# MCU.net
KiCad netlist of a schematic drawn in Altium Designer
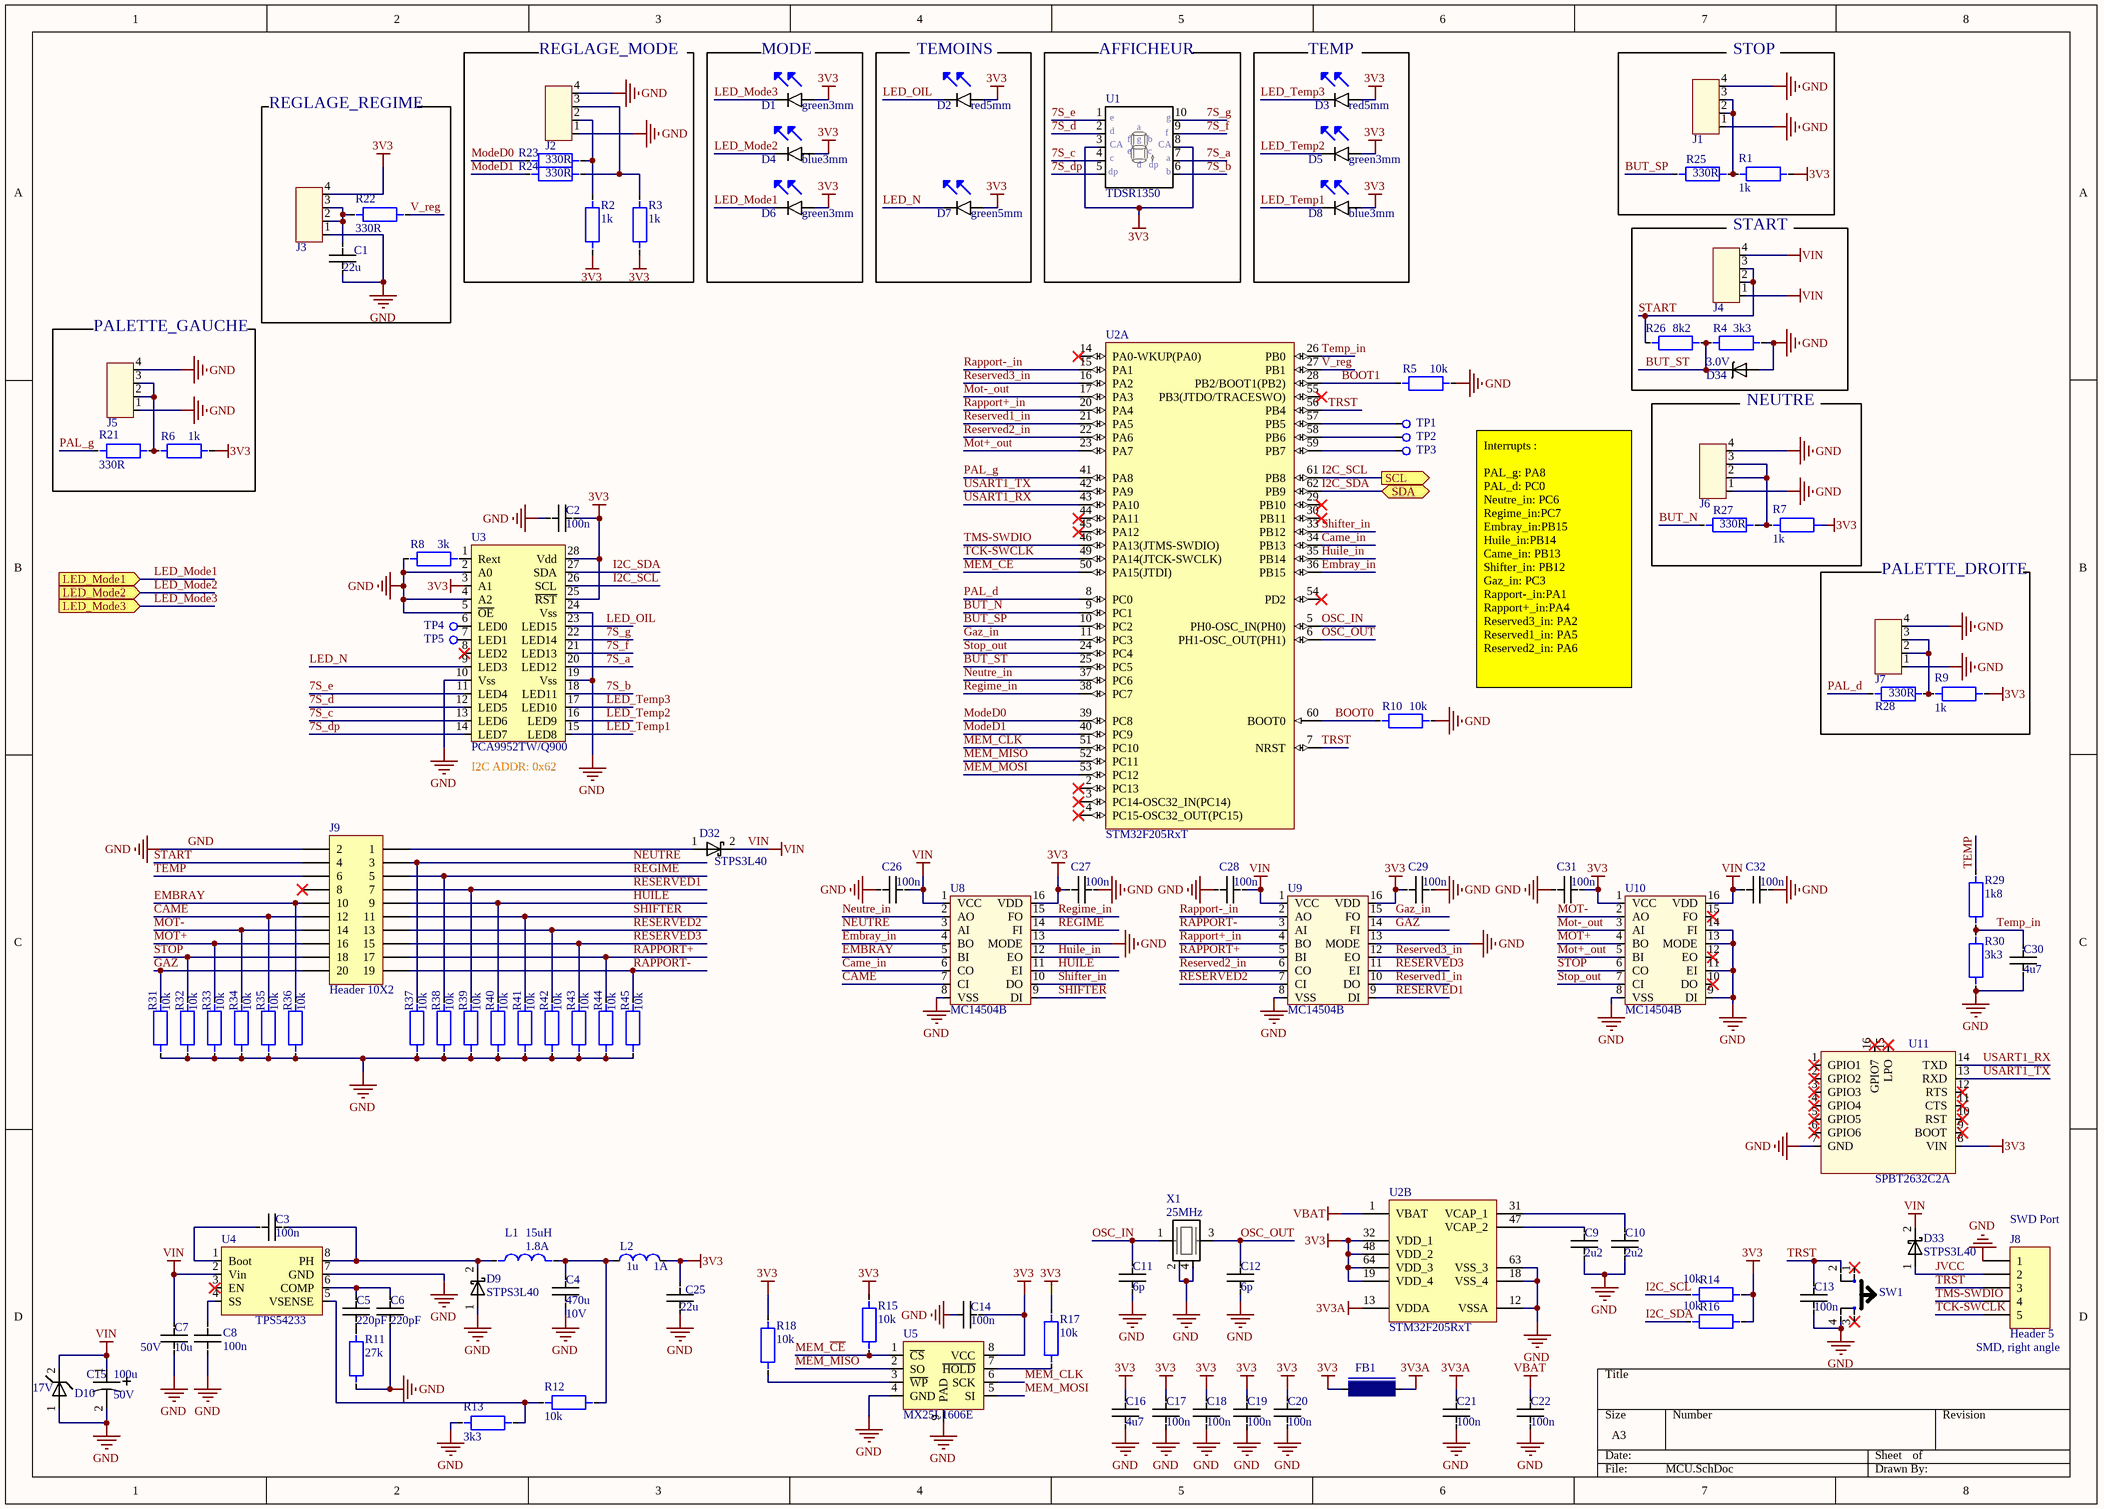
[diagram p0: MCU.SchDoc]

(export (version "E")
  (design (tool "Eeschema 10.0.6"))
  (components
    (comp (ref "C1")
      (value "22u")
      (footprint "0805_")
      (fields
        (field (name "MANUFACTURER PARTNUM") "GRM21BR61A226ME51L")
        (field (name "MANUFACTURER") "Murata")
      )
      (libsource (lib "*") (part "C"))
    )
    (comp (ref "C2")
      (value "100n")
      (footprint "0402_")
      (fields
        (field (name "MANUFACTURER PARTNUM") "C1005X5R1E104K050BC")
        (field (name "MANUFACTURER") "TDK Corp")
      )
      (libsource (lib "*") (part "C"))
    )
    (comp (ref "C3")
      (value "100n")
      (footprint "0402_")
      (fields
        (field (name "MANUFACTURER PARTNUM") "C1005X5R1E104K050BC")
        (field (name "MANUFACTURER") "TDK Corp")
      )
      (libsource (lib "*") (part "C"))
    )
    (comp (ref "C4")
      (value "470u")
      (footprint "2917")
      (fields
        (field (name "VOLTAGE") "10V")
        (field (name "MANUFACTURER PARTNUM") "T495X477K010ATE100")
        (field (name "MANUFACTURER") "Kemet")
        (field (name "Comment") "C")
      )
      (libsource (lib "*") (part "C"))
    )
    (comp (ref "C5")
      (value "220pF")
      (footprint "0402_")
      (fields
        (field (name "MANUFACTURER PARTNUM") "CL05B221KB5NNNC")
        (field (name "MANUFACTURER") "Samsung")
        (field (name "Comment") "C")
      )
      (libsource (lib "*") (part "C"))
    )
    (comp (ref "C6")
      (value "220pF")
      (footprint "0402_")
      (fields
        (field (name "MANUFACTURER PARTNUM") "CL05B221KB5NNNC")
        (field (name "MANUFACTURER") "Samsung")
        (field (name "Comment") "C")
      )
      (libsource (lib "*") (part "C"))
    )
    (comp (ref "C7")
      (value "10u")
      (footprint "1206_")
      (fields
        (field (name "RATED VOLTAGE") "50V")
        (field (name "MANUFACTURER PARTNUM") "CL31A106KBHNNNE")
        (field (name "MANUFACTURER") "Samsung")
      )
      (libsource (lib "*") (part "C"))
    )
    (comp (ref "C8")
      (value "100n")
      (footprint "0402_")
      (fields
        (field (name "MANUFACTURER PARTNUM") "C1005X5R1E104K050BC")
        (field (name "MANUFACTURER") "TDK Corp")
      )
      (libsource (lib "*") (part "C"))
    )
    (comp (ref "C9")
      (value "2u2")
      (footprint "0402_")
      (fields
        (field (name "MANUFACTURER PARTNUM") "GRM155R61A225KE95D")
        (field (name "MANUFACTURER") "Murata")
        (field (name "VOLTAGE") "10V")
      )
      (libsource (lib "*") (part "C"))
    )
    (comp (ref "C10")
      (value "2u2")
      (footprint "0402_")
      (fields
        (field (name "MANUFACTURER PARTNUM") "GRM155R61A225KE95D")
        (field (name "MANUFACTURER") "Murata")
        (field (name "VOLTAGE") "10V")
      )
      (libsource (lib "*") (part "C"))
    )
    (comp (ref "C11")
      (value "6p")
      (footprint "0402_")
      (fields (field (name "MANUFACTURER") "Samsung") (field (name "MANUFACTURER PARTNUM") "CL05C060DB5NCNC"))
      (libsource (lib "*") (part "C"))
    )
    (comp (ref "C12")
      (value "6p")
      (footprint "0402_")
      (fields (field (name "MANUFACTURER") "Samsung") (field (name "MANUFACTURER PARTNUM") "CL05C060DB5NCNC"))
      (libsource (lib "*") (part "C"))
    )
    (comp (ref "C13")
      (value "100n")
      (footprint "0402_")
      (fields
        (field (name "MANUFACTURER PARTNUM") "C1005X5R1E104K050BC")
        (field (name "MANUFACTURER") "TDK Corp")
      )
      (libsource (lib "*") (part "C"))
    )
    (comp (ref "C14")
      (value "100n")
      (footprint "0402_")
      (fields
        (field (name "MANUFACTURER PARTNUM") "C1005X5R1E104K050BC")
        (field (name "MANUFACTURER") "TDK Corp")
      )
      (libsource (lib "*") (part "C"))
    )
    (comp (ref "C15")
      (value "100u")
      (footprint "C_pol8x12mm")
      (fields
        (field (name "RATED VOLTAGE") "50V")
        (field (name "MANUFACTURER") "Nichicon")
        (field (name "MANUFACTURER PARTNUM") "UVR1H101MPD1TD")
        (field (name "Comment") "C_pol")
      )
      (libsource (lib "Sch_GB_lib") (part "C_pol"))
    )
    (comp (ref "C16")
      (value "4u7")
      (footprint "0402_")
      (fields
        (field (name "MANUFACTURER") "Murata")
        (field (name "MANUFACTURER PARTNUM") "GRM155R60J475ME47D")
      )
      (libsource (lib "*") (part "C"))
    )
    (comp (ref "C17")
      (value "100n")
      (footprint "0402_")
      (fields
        (field (name "MANUFACTURER PARTNUM") "C1005X5R1E104K050BC")
        (field (name "MANUFACTURER") "TDK Corp")
      )
      (libsource (lib "*") (part "C"))
    )
    (comp (ref "C18")
      (value "100n")
      (footprint "0402_")
      (fields
        (field (name "MANUFACTURER PARTNUM") "C1005X5R1E104K050BC")
        (field (name "MANUFACTURER") "TDK Corp")
      )
      (libsource (lib "*") (part "C"))
    )
    (comp (ref "C19")
      (value "100n")
      (footprint "0402_")
      (fields
        (field (name "MANUFACTURER PARTNUM") "C1005X5R1E104K050BC")
        (field (name "MANUFACTURER") "TDK Corp")
      )
      (libsource (lib "*") (part "C"))
    )
    (comp (ref "C20")
      (value "100n")
      (footprint "0402_")
      (fields
        (field (name "MANUFACTURER PARTNUM") "C1005X5R1E104K050BC")
        (field (name "MANUFACTURER") "TDK Corp")
      )
      (libsource (lib "*") (part "C"))
    )
    (comp (ref "C21")
      (value "100n")
      (footprint "0402_")
      (fields
        (field (name "MANUFACTURER PARTNUM") "C1005X5R1E104K050BC")
        (field (name "MANUFACTURER") "TDK Corp")
      )
      (libsource (lib "*") (part "C"))
    )
    (comp (ref "C22")
      (value "100n")
      (footprint "0402_")
      (fields
        (field (name "MANUFACTURER PARTNUM") "C1005X5R1E104K050BC")
        (field (name "MANUFACTURER") "TDK Corp")
      )
      (libsource (lib "*") (part "C"))
    )
    (comp (ref "C25")
      (value "22u")
      (footprint "0805_")
      (fields
        (field (name "MANUFACTURER PARTNUM") "GRM21BR61A226ME51L")
        (field (name "MANUFACTURER") "Murata")
      )
      (libsource (lib "*") (part "C"))
    )
    (comp (ref "C26")
      (value "100n")
      (footprint "0402_")
      (fields
        (field (name "MANUFACTURER PARTNUM") "C1005X5R1E104K050BC")
        (field (name "MANUFACTURER") "TDK Corp")
      )
      (libsource (lib "*") (part "C"))
    )
    (comp (ref "C27")
      (value "100n")
      (footprint "0402_")
      (fields
        (field (name "MANUFACTURER PARTNUM") "C1005X5R1E104K050BC")
        (field (name "MANUFACTURER") "TDK Corp")
      )
      (libsource (lib "*") (part "C"))
    )
    (comp (ref "C28")
      (value "100n")
      (footprint "0402_")
      (fields
        (field (name "MANUFACTURER PARTNUM") "C1005X5R1E104K050BC")
        (field (name "MANUFACTURER") "TDK Corp")
      )
      (libsource (lib "*") (part "C"))
    )
    (comp (ref "C29")
      (value "100n")
      (footprint "0402_")
      (fields
        (field (name "MANUFACTURER PARTNUM") "C1005X5R1E104K050BC")
        (field (name "MANUFACTURER") "TDK Corp")
      )
      (libsource (lib "*") (part "C"))
    )
    (comp (ref "C30")
      (value "4u7")
      (footprint "0402_")
      (fields
        (field (name "MANUFACTURER") "Murata")
        (field (name "MANUFACTURER PARTNUM") "GRM155R60J475ME47D")
      )
      (libsource (lib "*") (part "C"))
    )
    (comp (ref "C31")
      (value "100n")
      (footprint "0402_")
      (fields
        (field (name "MANUFACTURER PARTNUM") "C1005X5R1E104K050BC")
        (field (name "MANUFACTURER") "TDK Corp")
      )
      (libsource (lib "*") (part "C"))
    )
    (comp (ref "C32")
      (value "100n")
      (footprint "0402_")
      (fields
        (field (name "MANUFACTURER PARTNUM") "C1005X5R1E104K050BC")
        (field (name "MANUFACTURER") "TDK Corp")
      )
      (libsource (lib "*") (part "C"))
    )
    (comp (ref "D1")
      (value "led")
      (footprint "LED3MM_GREEN")
      (fields
        (field (name "MANUFACTURER") "Kingbright")
        (field (name "MANUFACTURER PARTNUM") "WP710A10LZGCK")
        (field (name "COLOR_DIAM") "green3mm")
      )
      (libsource (lib "*") (part "led"))
    )
    (comp (ref "D2")
      (value "led")
      (footprint "LED5MM_RED")
      (fields
        (field (name "MANUFACTURER") "Cree Inc")
        (field (name "MANUFACTURER PARTNUM") "C503B-RCN-CW0Z0AA1")
        (field (name "COLOR_DIAM") "red5mm")
      )
      (libsource (lib "*") (part "led"))
    )
    (comp (ref "D3")
      (value "led")
      (footprint "LED5MM_RED")
      (fields
        (field (name "MANUFACTURER") "Cree Inc")
        (field (name "MANUFACTURER PARTNUM") "C503B-RCN-CW0Z0AA1")
        (field (name "COLOR_DIAM") "red5mm")
      )
      (libsource (lib "*") (part "led"))
    )
    (comp (ref "D4")
      (value "led")
      (footprint "LED3MM_BLUE")
      (fields
        (field (name "MANUFACTURER") "Wuerth")
        (field (name "MANUFACTURER PARTNUM") "151033BS03000")
        (field (name "COLOR_DIAM") "blue3mm")
      )
      (libsource (lib "*") (part "led"))
    )
    (comp (ref "D5")
      (value "led")
      (footprint "LED3MM_GREEN")
      (fields
        (field (name "MANUFACTURER") "Kingbright")
        (field (name "MANUFACTURER PARTNUM") "WP710A10LZGCK")
        (field (name "COLOR_DIAM") "green3mm")
      )
      (libsource (lib "*") (part "led"))
    )
    (comp (ref "D6")
      (value "led")
      (footprint "LED3MM_GREEN")
      (fields
        (field (name "MANUFACTURER") "Kingbright")
        (field (name "MANUFACTURER PARTNUM") "WP710A10LZGCK")
        (field (name "COLOR_DIAM") "green3mm")
      )
      (libsource (lib "*") (part "led"))
    )
    (comp (ref "D7")
      (value "led")
      (footprint "LED5MM_GREEN")
      (fields
        (field (name "MANUFACTURER") "Kingbright")
        (field (name "MANUFACTURER PARTNUM") "WP7113LZGCK")
        (field (name "COLOR_DIAM") "green5mm")
      )
      (libsource (lib "*") (part "led"))
    )
    (comp (ref "D8")
      (value "led")
      (footprint "LED3MM_BLUE")
      (fields
        (field (name "MANUFACTURER") "Wuerth")
        (field (name "MANUFACTURER PARTNUM") "151033BS03000")
        (field (name "COLOR_DIAM") "blue3mm")
      )
      (libsource (lib "*") (part "led"))
    )
    (comp (ref "D9")
      (value "STPS3L40")
      (footprint "SMB_FLAT")
      (fields
        (field (name "MANUFACTURER PARTNUM") "STPS3L40UF")
        (field (name "MANUFACTURER") "STMicroelectronics")
      )
      (libsource (lib "Sch_GB_lib") (part "STPS3L40"))
    )
    (comp (ref "D10")
      (value "Zener")
      (footprint "1N5354")
      (fields
        (field (name "VZ") "17V")
        (field (name "MANUFACTURER") "ON Semi")
        (field (name "MANUFACTURER PARTNUM") "1N5354BG")
      )
      (libsource (lib "Sch_GB_lib") (part "Zener"))
    )
    (comp (ref "D32")
      (value "STPS3L40")
      (footprint "SMB_FLAT")
      (fields
        (field (name "MANUFACTURER PARTNUM") "STPS3L40UF")
        (field (name "MANUFACTURER") "STMicroelectronics")
      )
      (libsource (lib "Sch_GB_lib") (part "STPS3L40"))
    )
    (comp (ref "D33")
      (value "STPS3L40")
      (footprint "SMB_FLAT")
      (fields
        (field (name "MANUFACTURER PARTNUM") "STPS3L40UF")
        (field (name "MANUFACTURER") "STMicroelectronics")
      )
      (libsource (lib "Sch_GB_lib") (part "STPS3L40"))
    )
    (comp (ref "D34")
      (value "BZX384-C3V0")
      (footprint "SOD323")
      (description "DIODE ZENER 3V 300MW SOD323")
      (fields
        (field (name "MANUFACTURER PARTNUM") "BZX384-C3V0,115")
        (field (name "MANUFACTURER") "NXP")
        (field (name "VZ") "3.0V")
      )
      (libsource (lib "Sch_GB_lib") (part "BZX384-C3V0"))
    )
    (comp (ref "FB1")
      (value "FB")
      (footprint "0402_")
      (fields (field (name "MANUFACTURER") "Murata") (field (name "MANUFACTURER PARTNUM") "BLM15HG102SN1D"))
      (libsource (lib "SCH_lib_rey") (part "FB"))
    )
    (comp (ref "J1")
      (value "MOLEX_embase_4_voies")
      (footprint "MOLEX53047-0410")
      (description "53047-0410 MOLEX")
      (fields (field (name "MANUFACTURER PARTNUM") "0530470410") (field (name "MANUFACTURER") "Molex"))
      (libsource (lib "Sch_GB_lib") (part "MOLEX_embase_4_voies"))
    )
    (comp (ref "J2")
      (value "MOLEX_embase_4_voies")
      (footprint "MOLEX53047-0410")
      (description "53047-0410 MOLEX")
      (fields (field (name "MANUFACTURER PARTNUM") "0530470410") (field (name "MANUFACTURER") "Molex"))
      (libsource (lib "Sch_GB_lib") (part "MOLEX_embase_4_voies"))
    )
    (comp (ref "J3")
      (value "MOLEX_embase_4_voies")
      (footprint "MOLEX53047-0410")
      (description "53047-0410 MOLEX")
      (fields (field (name "MANUFACTURER PARTNUM") "0530470410") (field (name "MANUFACTURER") "Molex"))
      (libsource (lib "Sch_GB_lib") (part "MOLEX_embase_4_voies"))
    )
    (comp (ref "J4")
      (value "MOLEX_embase_4_voies")
      (footprint "MOLEX53047-0410")
      (description "53047-0410 MOLEX")
      (fields (field (name "MANUFACTURER PARTNUM") "0530470410") (field (name "MANUFACTURER") "Molex"))
      (libsource (lib "Sch_GB_lib") (part "MOLEX_embase_4_voies"))
    )
    (comp (ref "J5")
      (value "MOLEX_embase_4_voies")
      (footprint "MOLEX53047-0410")
      (description "53047-0410 MOLEX")
      (fields (field (name "MANUFACTURER PARTNUM") "0530470410") (field (name "MANUFACTURER") "Molex"))
      (libsource (lib "Sch_GB_lib") (part "MOLEX_embase_4_voies"))
    )
    (comp (ref "J6")
      (value "MOLEX_embase_4_voies")
      (footprint "MOLEX53047-0410")
      (description "53047-0410 MOLEX")
      (fields (field (name "MANUFACTURER PARTNUM") "0530470410") (field (name "MANUFACTURER") "Molex"))
      (libsource (lib "Sch_GB_lib") (part "MOLEX_embase_4_voies"))
    )
    (comp (ref "J7")
      (value "MOLEX_embase_4_voies")
      (footprint "MOLEX53047-0410")
      (description "53047-0410 MOLEX")
      (fields (field (name "MANUFACTURER PARTNUM") "0530470410") (field (name "MANUFACTURER") "Molex"))
      (libsource (lib "Sch_GB_lib") (part "MOLEX_embase_4_voies"))
    )
    (comp (ref "J8")
      (value "Header 5")
      (footprint "HDR1X5")
      (description "Header, 5-Pin")
      (fields
        (field (name "ALTIUM_VALUE") "SWD Port")
        (field (name "STATUS") "SMD, right angle")
        (field (name "MANUFACTURER") "TE Connectivity")
        (field (name "MANUFACTURER PARTNUM") "A9BAG-0502F")
        (field (name "PUBLISHER") "Altium Limited")
      )
      (libsource (lib "Sch_GB_lib") (part "Header 5"))
    )
    (comp (ref "J9")
      (value "Header 10X2")
      (footprint "header2x10")
      (description "Header, 10-Pin, Dual row")
      (fields
        (field (name "MANUFACTURER") "Harwin")
        (field (name "MANUFACTURER PARTNUM") "M20-9991046")
        (field (name "PUBLISHER") "Altium Limited")
      )
      (libsource (lib "Miscellaneous Connectors") (part "Header 10X2"))
    )
    (comp (ref "L1")
      (value "15uH")
      (footprint "SRN6028")
      (description "15µH Unshielded Wirewound Inductor 1.8A 114 mOhm Max Nonstandard")
      (fields
        (field (name "MANUFACTURER PARTNUM") "SRN6028-150M")
        (field (name "MANUFACTURER") "Bourns Inc")
        (field (name "CURRENT") "1.8A")
      )
      (libsource (lib "*") (part "L"))
    )
    (comp (ref "L2")
      (value "1u")
      (footprint "0805_")
      (fields
        (field (name "CURRENT") "1A")
        (field (name "MANUFACTURER PARTNUM") "BRC2012T1R0M")
        (field (name "MANUFACTURER") "Taiyo Yuden")
        (field (name "Comment") "Inductor")
      )
      (libsource (lib "Sch_GB_lib") (part "Inductor"))
    )
    (comp (ref "R1")
      (value "1k")
      (footprint "0402_")
      (fields (field (name "MANUFACTURER PARTNUM") "MCR01MRTF1001") (field (name "MANUFACTURER") "Rohm Semi"))
      (libsource (lib "*") (part "R"))
    )
    (comp (ref "R2")
      (value "1k")
      (footprint "0402_")
      (fields (field (name "MANUFACTURER PARTNUM") "MCR01MRTF1001") (field (name "MANUFACTURER") "Rohm Semi"))
      (libsource (lib "*") (part "R"))
    )
    (comp (ref "R3")
      (value "1k")
      (footprint "0402_")
      (fields (field (name "MANUFACTURER PARTNUM") "MCR01MRTF1001") (field (name "MANUFACTURER") "Rohm Semi"))
      (libsource (lib "*") (part "R"))
    )
    (comp (ref "R4") (value "3k3") (footprint "0402_") (libsource (lib "*") (part "R")))
    (comp (ref "R5")
      (value "10k")
      (footprint "0402_")
      (fields (field (name "MANUFACTURER") "Susumu") (field (name "MANUFACTURER PARTNUM") "RR0510P-103-D"))
      (libsource (lib "*") (part "R"))
    )
    (comp (ref "R6")
      (value "1k")
      (footprint "0402_")
      (fields (field (name "MANUFACTURER PARTNUM") "MCR01MRTF1001") (field (name "MANUFACTURER") "Rohm Semi"))
      (libsource (lib "*") (part "R"))
    )
    (comp (ref "R7")
      (value "1k")
      (footprint "0402_")
      (fields (field (name "MANUFACTURER PARTNUM") "MCR01MRTF1001") (field (name "MANUFACTURER") "Rohm Semi"))
      (libsource (lib "*") (part "R"))
    )
    (comp (ref "R8")
      (value "3k")
      (footprint "0402_")
      (fields (field (name "MANUFACTURER PARTNUM") "RC0402FR-073KL") (field (name "MANUFACTURER") "Yageo"))
      (libsource (lib "*") (part "R"))
    )
    (comp (ref "R9")
      (value "1k")
      (footprint "0402_")
      (fields (field (name "MANUFACTURER PARTNUM") "MCR01MRTF1001") (field (name "MANUFACTURER") "Rohm Semi"))
      (libsource (lib "*") (part "R"))
    )
    (comp (ref "R10")
      (value "10k")
      (footprint "0402_")
      (fields (field (name "MANUFACTURER") "Susumu") (field (name "MANUFACTURER PARTNUM") "RR0510P-103-D"))
      (libsource (lib "*") (part "R"))
    )
    (comp (ref "R11")
      (value "27k")
      (footprint "0402_")
      (fields (field (name "MANUFACTURER PARTNUM") "ERJ-2RKF2702X") (field (name "MANUFACTURER") "Panasonic"))
      (libsource (lib "*") (part "R"))
    )
    (comp (ref "R12")
      (value "10k")
      (footprint "0402_")
      (fields (field (name "MANUFACTURER PARTNUM") "ERJ-2RKF1002X") (field (name "MANUFACTURER") "Panasonic"))
      (libsource (lib "*") (part "R"))
    )
    (comp (ref "R13")
      (value "3k3")
      (footprint "0402_")
      (fields (field (name "MANUFACTURER PARTNUM") "ERJ-2RKF3301X") (field (name "MANUFACTURER") "Panasonic"))
      (libsource (lib "*") (part "R"))
    )
    (comp (ref "R14")
      (value "10k")
      (footprint "0402_")
      (fields (field (name "MANUFACTURER PARTNUM") "ERJ-2RKF1002X") (field (name "MANUFACTURER") "Panasonic"))
      (libsource (lib "*") (part "R"))
    )
    (comp (ref "R15")
      (value "10k")
      (footprint "0402_")
      (fields (field (name "MANUFACTURER PARTNUM") "ERJ-2RKF1002X") (field (name "MANUFACTURER") "Panasonic"))
      (libsource (lib "*") (part "R"))
    )
    (comp (ref "R16")
      (value "10k")
      (footprint "0402_")
      (fields (field (name "MANUFACTURER PARTNUM") "ERJ-2RKF1002X") (field (name "MANUFACTURER") "Panasonic"))
      (libsource (lib "*") (part "R"))
    )
    (comp (ref "R17")
      (value "10k")
      (footprint "0402_")
      (fields (field (name "MANUFACTURER PARTNUM") "ERJ-2RKF1002X") (field (name "MANUFACTURER") "Panasonic"))
      (libsource (lib "*") (part "R"))
    )
    (comp (ref "R18")
      (value "10k")
      (footprint "0402_")
      (fields (field (name "MANUFACTURER PARTNUM") "ERJ-2RKF1002X") (field (name "MANUFACTURER") "Panasonic"))
      (libsource (lib "*") (part "R"))
    )
    (comp (ref "R21")
      (value "330R")
      (footprint "0402_")
      (fields (field (name "MANUFACTURER PARTNUM") "RC0402JR-07330RL") (field (name "MANUFACTURER") "Yageo"))
      (libsource (lib "lib_lupo") (part "R"))
    )
    (comp (ref "R22")
      (value "330R")
      (footprint "0402_")
      (fields (field (name "MANUFACTURER PARTNUM") "RC0402JR-07330RL") (field (name "MANUFACTURER") "Yageo"))
      (libsource (lib "lib_lupo") (part "R"))
    )
    (comp (ref "R23")
      (value "330R")
      (footprint "0402_")
      (fields (field (name "MANUFACTURER PARTNUM") "RC0402JR-07330RL") (field (name "MANUFACTURER") "Yageo"))
      (libsource (lib "lib_lupo") (part "R"))
    )
    (comp (ref "R24")
      (value "330R")
      (footprint "0402_")
      (fields (field (name "MANUFACTURER PARTNUM") "RC0402JR-07330RL") (field (name "MANUFACTURER") "Yageo"))
      (libsource (lib "lib_lupo") (part "R"))
    )
    (comp (ref "R25")
      (value "330R")
      (footprint "0402_")
      (fields (field (name "MANUFACTURER PARTNUM") "RC0402JR-07330RL") (field (name "MANUFACTURER") "Yageo"))
      (libsource (lib "lib_lupo") (part "R"))
    )
    (comp (ref "R26") (value "8k2") (footprint "0402_") (libsource (lib "*") (part "R")))
    (comp (ref "R27")
      (value "330R")
      (footprint "0402_")
      (fields (field (name "MANUFACTURER PARTNUM") "RC0402JR-07330RL") (field (name "MANUFACTURER") "Yageo"))
      (libsource (lib "lib_lupo") (part "R"))
    )
    (comp (ref "R28")
      (value "330R")
      (footprint "0402_")
      (fields (field (name "MANUFACTURER PARTNUM") "RC0402JR-07330RL") (field (name "MANUFACTURER") "Yageo"))
      (libsource (lib "lib_lupo") (part "R"))
    )
    (comp (ref "R29")
      (value "1k8")
      (footprint "0402_")
      (fields (field (name "MANUFACTURER PARTNUM") "RC0402FR-071K8L") (field (name "MANUFACTURER") "Yageo"))
      (libsource (lib "*") (part "R"))
    )
    (comp (ref "R30")
      (value "3k3")
      (footprint "0402_")
      (fields (field (name "MANUFACTURER PARTNUM") "RC0402FR-073K3L") (field (name "MANUFACTURER") "Yageo"))
      (libsource (lib "*") (part "R"))
    )
    (comp (ref "R31")
      (value "10k")
      (footprint "0402_")
      (fields (field (name "MANUFACTURER") "Susumu") (field (name "MANUFACTURER PARTNUM") "RR0510P-103-D"))
      (libsource (lib "*") (part "R"))
    )
    (comp (ref "R32")
      (value "10k")
      (footprint "0402_")
      (fields (field (name "MANUFACTURER") "Susumu") (field (name "MANUFACTURER PARTNUM") "RR0510P-103-D"))
      (libsource (lib "*") (part "R"))
    )
    (comp (ref "R33")
      (value "10k")
      (footprint "0402_")
      (fields (field (name "MANUFACTURER") "Susumu") (field (name "MANUFACTURER PARTNUM") "RR0510P-103-D"))
      (libsource (lib "*") (part "R"))
    )
    (comp (ref "R34")
      (value "10k")
      (footprint "0402_")
      (fields (field (name "MANUFACTURER") "Susumu") (field (name "MANUFACTURER PARTNUM") "RR0510P-103-D"))
      (libsource (lib "*") (part "R"))
    )
    (comp (ref "R35")
      (value "10k")
      (footprint "0402_")
      (fields (field (name "MANUFACTURER") "Susumu") (field (name "MANUFACTURER PARTNUM") "RR0510P-103-D"))
      (libsource (lib "*") (part "R"))
    )
    (comp (ref "R36")
      (value "10k")
      (footprint "0402_")
      (fields (field (name "MANUFACTURER") "Susumu") (field (name "MANUFACTURER PARTNUM") "RR0510P-103-D"))
      (libsource (lib "*") (part "R"))
    )
    (comp (ref "R37")
      (value "10k")
      (footprint "0402_")
      (fields (field (name "MANUFACTURER") "Susumu") (field (name "MANUFACTURER PARTNUM") "RR0510P-103-D"))
      (libsource (lib "*") (part "R"))
    )
    (comp (ref "R38")
      (value "10k")
      (footprint "0402_")
      (fields (field (name "MANUFACTURER") "Susumu") (field (name "MANUFACTURER PARTNUM") "RR0510P-103-D"))
      (libsource (lib "*") (part "R"))
    )
    (comp (ref "R39")
      (value "10k")
      (footprint "0402_")
      (fields (field (name "MANUFACTURER") "Susumu") (field (name "MANUFACTURER PARTNUM") "RR0510P-103-D"))
      (libsource (lib "*") (part "R"))
    )
    (comp (ref "R40")
      (value "10k")
      (footprint "0402_")
      (fields (field (name "MANUFACTURER") "Susumu") (field (name "MANUFACTURER PARTNUM") "RR0510P-103-D"))
      (libsource (lib "*") (part "R"))
    )
    (comp (ref "R41")
      (value "10k")
      (footprint "0402_")
      (fields (field (name "MANUFACTURER") "Susumu") (field (name "MANUFACTURER PARTNUM") "RR0510P-103-D"))
      (libsource (lib "*") (part "R"))
    )
    (comp (ref "R42")
      (value "10k")
      (footprint "0402_")
      (fields (field (name "MANUFACTURER") "Susumu") (field (name "MANUFACTURER PARTNUM") "RR0510P-103-D"))
      (libsource (lib "*") (part "R"))
    )
    (comp (ref "R43")
      (value "10k")
      (footprint "0402_")
      (fields (field (name "MANUFACTURER") "Susumu") (field (name "MANUFACTURER PARTNUM") "RR0510P-103-D"))
      (libsource (lib "*") (part "R"))
    )
    (comp (ref "R44")
      (value "10k")
      (footprint "0402_")
      (fields (field (name "MANUFACTURER") "Susumu") (field (name "MANUFACTURER PARTNUM") "RR0510P-103-D"))
      (libsource (lib "*") (part "R"))
    )
    (comp (ref "R45")
      (value "10k")
      (footprint "0402_")
      (fields (field (name "MANUFACTURER") "Susumu") (field (name "MANUFACTURER PARTNUM") "RR0510P-103-D"))
      (libsource (lib "*") (part "R"))
    )
    (comp (ref "SW1")
      (value "switch")
      (footprint "microswitch_PTS810")
      (fields
        (field (name "MANUFACTURER") "C&K")
        (field (name "MANUFACTURER PARTNUM") "PTS810 SJM 250 SMTR LFS")
      )
      (libsource (lib "Sch_GB_lib") (part "switch"))
    )
    (comp (ref "TP1") (value "TP") (footprint "TP_PogoPin") (libsource (lib "Sch_GB_lib") (part "TP")))
    (comp (ref "TP2") (value "TP") (footprint "TP_PogoPin") (libsource (lib "Sch_GB_lib") (part "TP")))
    (comp (ref "TP3") (value "TP") (footprint "TP_PogoPin") (libsource (lib "Sch_GB_lib") (part "TP")))
    (comp (ref "TP4") (value "TP") (footprint "TP_PogoPin") (libsource (lib "Sch_GB_lib") (part "TP")))
    (comp (ref "TP5") (value "TP") (footprint "TP_PogoPin") (libsource (lib "Sch_GB_lib") (part "TP")))
    (comp (ref "U1")
      (value "TDSR1350")
      (footprint "TDSR1350")
      (fields (field (name "MANUFACTURER") "Vishay Semi"))
      (libsource (lib "Sch_GB_lib") (part "TDSR1350"))
    )
    (comp (ref "U2")
      (value "STM32F205RxT")
      (footprint "LQFP64")
      (fields
        (field (name "MANUFACTURER") "ST Microelectronics")
        (field (name "MANUFACTURER PARTNUM") "STM32F205RCT6")
      )
      (libsource (lib "Sch_GB_lib") (part "STM32F205RxT"))
    )
    (comp (ref "U3")
      (value "PCA9952TW/Q900")
      (footprint "HTSSOP28")
      (fields (field (name "MANUFACTURER") "NXP") (field (name "MANUFACTURER PARTNUM") "PCA9952TW/Q900,118"))
      (libsource (lib "Sch_GB_lib") (part "PCA9952TW/Q900"))
    )
    (comp (ref "U4")
      (value "TPS54233")
      (footprint "soic8")
      (description "Buck Switching Regulator IC Positive Adjustable 0.8V 1 Output 2A 8-SOIC (0.154\", 3.90mm Width)")
      (fields
        (field (name "MANUFACTURER") "Texas Instruments")
        (field (name "MANUFACTURER PARTNUM") "TPS54233DR")
      )
      (libsource (lib "*") (part "TPS54233"))
    )
    (comp (ref "U5")
      (value "MX25L1606E")
      (footprint "USON_8L")
      (description "16M-BIT [x 1 / x 2] CMOS SERIAL FLASH, 4KB Sector Erase")
      (fields
        (field (name "MANUFACTURER PARTNUM") "MX25L1606EZUI-12G")
        (field (name "MANUFACTURER") "Macronix")
      )
      (libsource (lib "Sch_GB_lib") (part "MX25L1606E"))
    )
    (comp (ref "U8")
      (value "MC14504B")
      (footprint "SOIC16")
      (description "IC LEVEL SHIFTER HEX 16-SOIC")
      (fields (field (name "MANUFACTURER") "On Semi") (field (name "MANUFACTURER PARTNUM") "MC14504BDG"))
      (libsource (lib "Sch_GB_lib") (part "MC14504B"))
    )
    (comp (ref "U9")
      (value "MC14504B")
      (footprint "SOIC16")
      (description "IC LEVEL SHIFTER HEX 16-SOIC")
      (fields (field (name "MANUFACTURER") "On Semi") (field (name "MANUFACTURER PARTNUM") "MC14504BDG"))
      (libsource (lib "Sch_GB_lib") (part "MC14504B"))
    )
    (comp (ref "U10")
      (value "MC14504B")
      (footprint "SOIC16")
      (description "IC LEVEL SHIFTER HEX 16-SOIC")
      (fields (field (name "MANUFACTURER") "On Semi") (field (name "MANUFACTURER PARTNUM") "MC14504BDG"))
      (libsource (lib "Sch_GB_lib") (part "MC14504B"))
    )
    (comp (ref "U11")
      (value "SPBT2632C2A")
      (footprint "SPBT2632C2A")
      (fields
        (field (name "MANUFACTURER") "ST Microelectronics")
        (field (name "MANUFACTURER PARTNUM") "SPBT2632C2A.AT2")
      )
      (libsource (lib "Sch_GB_lib") (part "SPBT2632C2A"))
    )
    (comp (ref "X1")
      (value "25MHz")
      (footprint "FA_128")
      (fields
        (field (name "MANUFACTURER PARTNUM") "8Y-25.000MAAV-T")
        (field (name "MANUFACTURER") "TXC Corp.")
        (field (name "Comment") "QUARTZ")
      )
      (libsource (lib "Sch_GB_lib") (part "QUARTZ"))
    )
  )
  (nets
    (net (code "1") (name "/7S_a") (class "Default")
      (node (ref "U1") (pin "7") (pinfunction "7_7") (pintype "passive"))
      (node (ref "U3") (pin "20") (pinfunction "LED12_20") (pintype "passive"))
    )
    (net (code "2") (name "/7S_b") (class "Default")
      (node (ref "U1") (pin "6") (pinfunction "6_6") (pintype "passive"))
      (node (ref "U3") (pin "18") (pinfunction "LED11_18") (pintype "passive"))
    )
    (net (code "3") (name "/7S_c") (class "Default")
      (node (ref "U1") (pin "4") (pinfunction "4_4") (pintype "passive"))
      (node (ref "U3") (pin "13") (pinfunction "LED6_13") (pintype "passive"))
    )
    (net (code "4") (name "/7S_d") (class "Default")
      (node (ref "U1") (pin "2") (pinfunction "2_2") (pintype "passive"))
      (node (ref "U3") (pin "12") (pinfunction "LED5_12") (pintype "passive"))
    )
    (net (code "5") (name "/7S_dp") (class "Default")
      (node (ref "U1") (pin "5") (pinfunction "5_5") (pintype "passive"))
      (node (ref "U3") (pin "14") (pinfunction "LED7_14") (pintype "passive"))
    )
    (net (code "6") (name "/7S_e") (class "Default")
      (node (ref "U1") (pin "1") (pinfunction "1_1") (pintype "passive"))
      (node (ref "U3") (pin "11") (pinfunction "LED4_11") (pintype "passive"))
    )
    (net (code "7") (name "/7S_f") (class "Default")
      (node (ref "U1") (pin "9") (pinfunction "9_9") (pintype "passive"))
      (node (ref "U3") (pin "21") (pinfunction "LED13_21") (pintype "passive"))
    )
    (net (code "8") (name "/7S_g") (class "Default")
      (node (ref "U1") (pin "10") (pinfunction "10_10") (pintype "passive"))
      (node (ref "U3") (pin "22") (pinfunction "LED14_22") (pintype "passive"))
    )
    (net (code "9") (name "/BOOT0") (class "Default")
      (node (ref "R10") (pin "1") (pinfunction "1_1") (pintype "passive"))
      (node (ref "U2") (pin "60") (pinfunction "BOOT0_60") (pintype "input"))
    )
    (net (code "10") (name "/BOOT1") (class "Default")
      (node (ref "R5") (pin "1") (pinfunction "1_1") (pintype "passive"))
      (node (ref "U2") (pin "28") (pinfunction "PB2/BOOT1(PB2)_28") (pintype "bidirectional"))
    )
    (net (code "11") (name "/BUT_N") (class "Default")
      (node (ref "R27") (pin "2") (pinfunction "2_2") (pintype "passive"))
      (node (ref "U2") (pin "9") (pinfunction "PC1_9") (pintype "bidirectional"))
    )
    (net (code "12") (name "/BUT_SP") (class "Default")
      (node (ref "R25") (pin "2") (pinfunction "2_2") (pintype "passive"))
      (node (ref "U2") (pin "10") (pinfunction "PC2_10") (pintype "bidirectional"))
    )
    (net (code "13") (name "/BUT_ST") (class "Default")
      (node (ref "D34") (pin "2") (pinfunction "2_2") (pintype "passive"))
      (node (ref "R26") (pin "1") (pinfunction "1_1") (pintype "passive"))
      (node (ref "R4") (pin "2") (pinfunction "2_2") (pintype "passive"))
      (node (ref "U2") (pin "25") (pinfunction "PC5_25") (pintype "bidirectional"))
    )
    (net (code "14") (name "/CAME") (class "Default")
      (node (ref "J9") (pin "12") (pinfunction "12_12") (pintype "passive"))
      (node (ref "R35") (pin "2") (pinfunction "2_2") (pintype "passive"))
      (node (ref "U8") (pin "7") (pinfunction "CI_7") (pintype "passive"))
    )
    (net (code "15") (name "/Came_in") (class "Default")
      (node (ref "U2") (pin "34") (pinfunction "PB13_34") (pintype "bidirectional"))
      (node (ref "U8") (pin "6") (pinfunction "CO_6") (pintype "passive"))
    )
    (net (code "16") (name "/EMBRAY") (class "Default")
      (node (ref "J9") (pin "10") (pinfunction "10_10") (pintype "passive"))
      (node (ref "R36") (pin "2") (pinfunction "2_2") (pintype "passive"))
      (node (ref "U8") (pin "5") (pinfunction "BI_5") (pintype "passive"))
    )
    (net (code "17") (name "/Embray_in") (class "Default")
      (node (ref "U2") (pin "36") (pinfunction "PB15_36") (pintype "bidirectional"))
      (node (ref "U8") (pin "4") (pinfunction "BO_4") (pintype "passive"))
    )
    (net (code "18") (name "/GAZ") (class "Default")
      (node (ref "J9") (pin "20") (pinfunction "20_20") (pintype "passive"))
      (node (ref "R31") (pin "2") (pinfunction "2_2") (pintype "passive"))
      (node (ref "U9") (pin "14") (pinfunction "FI_14") (pintype "passive"))
    )
    (net (code "19") (name "/Gaz_in") (class "Default")
      (node (ref "U2") (pin "11") (pinfunction "PC3_11") (pintype "bidirectional"))
      (node (ref "U9") (pin "15") (pinfunction "FO_15") (pintype "passive"))
    )
    (net (code "20") (name "/HUILE") (class "Default")
      (node (ref "J9") (pin "9") (pinfunction "9_9") (pintype "passive"))
      (node (ref "R40") (pin "2") (pinfunction "2_2") (pintype "passive"))
      (node (ref "U8") (pin "11") (pinfunction "EI_11") (pintype "passive"))
    )
    (net (code "21") (name "/Huile_in") (class "Default")
      (node (ref "U2") (pin "35") (pinfunction "PB14_35") (pintype "bidirectional"))
      (node (ref "U8") (pin "12") (pinfunction "EO_12") (pintype "passive"))
    )
    (net (code "22") (name "/I2C_SCL") (class "Default")
      (node (ref "R14") (pin "2") (pinfunction "2_2") (pintype "passive"))
      (node (ref "U2") (pin "61") (pinfunction "PB8_61") (pintype "bidirectional"))
      (node (ref "U3") (pin "26") (pinfunction "SCL_26") (pintype "passive"))
    )
    (net (code "23") (name "/I2C_SDA") (class "Default")
      (node (ref "R16") (pin "2") (pinfunction "2_2") (pintype "passive"))
      (node (ref "U2") (pin "62") (pinfunction "PB9_62") (pintype "bidirectional"))
      (node (ref "U3") (pin "27") (pinfunction "SDA_27") (pintype "passive"))
    )
    (net (code "24") (name "/JVCC") (class "Default")
      (node (ref "D33") (pin "1") (pinfunction "A_1") (pintype "passive"))
      (node (ref "J8") (pin "2") (pinfunction "2_2") (pintype "passive"))
    )
    (net (code "25") (name "/LED_Mode1") (class "Default")
      (node (ref "D6") (pin "2") (pinfunction "2_2") (pintype "passive"))
    )
    (net (code "26") (name "/LED_Mode2") (class "Default")
      (node (ref "D4") (pin "2") (pinfunction "2_2") (pintype "passive"))
    )
    (net (code "27") (name "/LED_Mode3") (class "Default")
      (node (ref "D1") (pin "2") (pinfunction "2_2") (pintype "passive"))
    )
    (net (code "28") (name "/LED_N") (class "Default")
      (node (ref "D7") (pin "2") (pinfunction "2_2") (pintype "passive"))
      (node (ref "U3") (pin "9") (pinfunction "LED3_9") (pintype "passive"))
    )
    (net (code "29") (name "/LED_OIL") (class "Default")
      (node (ref "D2") (pin "2") (pinfunction "2_2") (pintype "passive"))
      (node (ref "U3") (pin "23") (pinfunction "LED15_23") (pintype "passive"))
    )
    (net (code "30") (name "/LED_Temp1") (class "Default")
      (node (ref "D8") (pin "2") (pinfunction "2_2") (pintype "passive"))
      (node (ref "U3") (pin "15") (pinfunction "LED8_15") (pintype "passive"))
    )
    (net (code "31") (name "/LED_Temp2") (class "Default")
      (node (ref "D5") (pin "2") (pinfunction "2_2") (pintype "passive"))
      (node (ref "U3") (pin "16") (pinfunction "LED9_16") (pintype "passive"))
    )
    (net (code "32") (name "/LED_Temp3") (class "Default")
      (node (ref "D3") (pin "2") (pinfunction "2_2") (pintype "passive"))
      (node (ref "U3") (pin "17") (pinfunction "LED10_17") (pintype "passive"))
    )
    (net (code "33") (name "/MEM_CLK") (class "Default")
      (node (ref "U2") (pin "51") (pinfunction "PC10_51") (pintype "bidirectional"))
      (node (ref "U5") (pin "6") (pinfunction "SCK_6") (pintype "passive"))
    )
    (net (code "34") (name "/MEM_MISO") (class "Default")
      (node (ref "U2") (pin "52") (pinfunction "PC11_52") (pintype "bidirectional"))
      (node (ref "U5") (pin "2") (pinfunction "SO_2") (pintype "passive"))
    )
    (net (code "35") (name "/MEM_MOSI") (class "Default")
      (node (ref "U2") (pin "53") (pinfunction "PC12_53") (pintype "bidirectional"))
      (node (ref "U5") (pin "5") (pinfunction "SI_5") (pintype "passive"))
    )
    (net (code "36") (name "/MEM_~{CE}") (class "Default")
      (node (ref "R15") (pin "2") (pinfunction "2_2") (pintype "passive"))
      (node (ref "U2") (pin "50") (pinfunction "PA15(JTDI)_50") (pintype "bidirectional"))
      (node (ref "U5") (pin "1") (pinfunction "~{CS}_1") (pintype "passive"))
    )
    (net (code "37") (name "/MOT+") (class "Default")
      (node (ref "J9") (pin "16") (pinfunction "16_16") (pintype "passive"))
      (node (ref "R33") (pin "2") (pinfunction "2_2") (pintype "passive"))
      (node (ref "U10") (pin "4") (pinfunction "BO_4") (pintype "passive"))
    )
    (net (code "38") (name "/MOT-") (class "Default")
      (node (ref "J9") (pin "14") (pinfunction "14_14") (pintype "passive"))
      (node (ref "R34") (pin "2") (pinfunction "2_2") (pintype "passive"))
      (node (ref "U10") (pin "2") (pinfunction "AO_2") (pintype "passive"))
    )
    (net (code "39") (name "/ModeD0") (class "Default")
      (node (ref "R23") (pin "2") (pinfunction "2_2") (pintype "passive"))
      (node (ref "U2") (pin "39") (pinfunction "PC8_39") (pintype "bidirectional"))
    )
    (net (code "40") (name "/ModeD1") (class "Default")
      (node (ref "R24") (pin "2") (pinfunction "2_2") (pintype "passive"))
      (node (ref "U2") (pin "40") (pinfunction "PC9_40") (pintype "bidirectional"))
    )
    (net (code "41") (name "/Mot+_out") (class "Default")
      (node (ref "U10") (pin "5") (pinfunction "BI_5") (pintype "passive"))
      (node (ref "U2") (pin "23") (pinfunction "PA7_23") (pintype "bidirectional"))
    )
    (net (code "42") (name "/Mot-_out") (class "Default")
      (node (ref "U10") (pin "3") (pinfunction "AI_3") (pintype "passive"))
      (node (ref "U2") (pin "17") (pinfunction "PA3_17") (pintype "bidirectional"))
    )
    (net (code "43") (name "/NEUTRE") (class "Default")
      (node (ref "J9") (pin "3") (pinfunction "3_3") (pintype "passive"))
      (node (ref "R37") (pin "2") (pinfunction "2_2") (pintype "passive"))
      (node (ref "U8") (pin "3") (pinfunction "AI_3") (pintype "passive"))
    )
    (net (code "44") (name "/Neutre_in") (class "Default")
      (node (ref "U2") (pin "37") (pinfunction "PC6_37") (pintype "bidirectional"))
      (node (ref "U8") (pin "2") (pinfunction "AO_2") (pintype "passive"))
    )
    (net (code "45") (name "/OSC_IN") (class "Default")
      (node (ref "C11") (pin "2") (pinfunction "2_2") (pintype "passive"))
      (node (ref "U2") (pin "5") (pinfunction "PH0-OSC_IN(PH0)_5") (pintype "bidirectional"))
      (node (ref "X1") (pin "1") (pinfunction "1_1") (pintype "passive"))
    )
    (net (code "46") (name "/OSC_OUT") (class "Default")
      (node (ref "C12") (pin "2") (pinfunction "2_2") (pintype "passive"))
      (node (ref "U2") (pin "6") (pinfunction "PH1-OSC_OUT(PH1)_6") (pintype "bidirectional"))
      (node (ref "X1") (pin "3") (pinfunction "3_3") (pintype "passive"))
    )
    (net (code "47") (name "/PAL_d") (class "Default")
      (node (ref "R28") (pin "2") (pinfunction "2_2") (pintype "passive"))
      (node (ref "U2") (pin "8") (pinfunction "PC0_8") (pintype "bidirectional"))
    )
    (net (code "48") (name "/PAL_g") (class "Default")
      (node (ref "R21") (pin "2") (pinfunction "2_2") (pintype "passive"))
      (node (ref "U2") (pin "41") (pinfunction "PA8_41") (pintype "bidirectional"))
    )
    (net (code "49") (name "/RAPPORT+") (class "Default")
      (node (ref "J9") (pin "17") (pinfunction "17_17") (pintype "passive"))
      (node (ref "R44") (pin "2") (pinfunction "2_2") (pintype "passive"))
      (node (ref "U9") (pin "5") (pinfunction "BI_5") (pintype "passive"))
    )
    (net (code "50") (name "/RAPPORT-") (class "Default")
      (node (ref "J9") (pin "19") (pinfunction "19_19") (pintype "passive"))
      (node (ref "R45") (pin "2") (pinfunction "2_2") (pintype "passive"))
      (node (ref "U9") (pin "3") (pinfunction "AI_3") (pintype "passive"))
    )
    (net (code "51") (name "/REGIME") (class "Default")
      (node (ref "J9") (pin "5") (pinfunction "5_5") (pintype "passive"))
      (node (ref "R38") (pin "2") (pinfunction "2_2") (pintype "passive"))
      (node (ref "U8") (pin "14") (pinfunction "FI_14") (pintype "passive"))
    )
    (net (code "52") (name "/RESERVED1") (class "Default")
      (node (ref "J9") (pin "7") (pinfunction "7_7") (pintype "passive"))
      (node (ref "R39") (pin "2") (pinfunction "2_2") (pintype "passive"))
      (node (ref "U9") (pin "9") (pinfunction "DI_9") (pintype "passive"))
    )
    (net (code "53") (name "/RESERVED2") (class "Default")
      (node (ref "J9") (pin "13") (pinfunction "13_13") (pintype "passive"))
      (node (ref "R42") (pin "2") (pinfunction "2_2") (pintype "passive"))
      (node (ref "U9") (pin "7") (pinfunction "CI_7") (pintype "passive"))
    )
    (net (code "54") (name "/RESERVED3") (class "Default")
      (node (ref "J9") (pin "15") (pinfunction "15_15") (pintype "passive"))
      (node (ref "R43") (pin "2") (pinfunction "2_2") (pintype "passive"))
      (node (ref "U9") (pin "11") (pinfunction "EI_11") (pintype "passive"))
    )
    (net (code "55") (name "/Rapport+_in") (class "Default")
      (node (ref "U2") (pin "20") (pinfunction "PA4_20") (pintype "bidirectional"))
      (node (ref "U9") (pin "4") (pinfunction "BO_4") (pintype "passive"))
    )
    (net (code "56") (name "/Rapport-_in") (class "Default")
      (node (ref "U2") (pin "15") (pinfunction "PA1_15") (pintype "bidirectional"))
      (node (ref "U9") (pin "2") (pinfunction "AO_2") (pintype "passive"))
    )
    (net (code "57") (name "/Regime_in") (class "Default")
      (node (ref "U2") (pin "38") (pinfunction "PC7_38") (pintype "bidirectional"))
      (node (ref "U8") (pin "15") (pinfunction "FO_15") (pintype "passive"))
    )
    (net (code "58") (name "/Reserved1_in") (class "Default")
      (node (ref "U2") (pin "21") (pinfunction "PA5_21") (pintype "bidirectional"))
      (node (ref "U9") (pin "10") (pinfunction "DO_10") (pintype "passive"))
    )
    (net (code "59") (name "/Reserved2_in") (class "Default")
      (node (ref "U2") (pin "22") (pinfunction "PA6_22") (pintype "bidirectional"))
      (node (ref "U9") (pin "6") (pinfunction "CO_6") (pintype "passive"))
    )
    (net (code "60") (name "/Reserved3_in") (class "Default")
      (node (ref "U2") (pin "16") (pinfunction "PA2_16") (pintype "bidirectional"))
      (node (ref "U9") (pin "12") (pinfunction "EO_12") (pintype "passive"))
    )
    (net (code "61") (name "/SHIFTER") (class "Default")
      (node (ref "J9") (pin "11") (pinfunction "11_11") (pintype "passive"))
      (node (ref "R41") (pin "2") (pinfunction "2_2") (pintype "passive"))
      (node (ref "U8") (pin "9") (pinfunction "DI_9") (pintype "passive"))
    )
    (net (code "62") (name "/START") (class "Default")
      (node (ref "J4") (pin "2") (pintype "passive"))
      (node (ref "J4") (pin "3") (pintype "passive"))
      (node (ref "J9") (pin "4") (pinfunction "4_4") (pintype "passive"))
      (node (ref "R26") (pin "2") (pinfunction "2_2") (pintype "passive"))
    )
    (net (code "63") (name "/STOP") (class "Default")
      (node (ref "J9") (pin "18") (pinfunction "18_18") (pintype "passive"))
      (node (ref "R32") (pin "2") (pinfunction "2_2") (pintype "passive"))
      (node (ref "U10") (pin "6") (pinfunction "CO_6") (pintype "passive"))
    )
    (net (code "64") (name "/Shifter_in") (class "Default")
      (node (ref "U2") (pin "33") (pinfunction "PB12_33") (pintype "bidirectional"))
      (node (ref "U8") (pin "10") (pinfunction "DO_10") (pintype "passive"))
    )
    (net (code "65") (name "/Stop_out") (class "Default")
      (node (ref "U10") (pin "7") (pinfunction "CI_7") (pintype "passive"))
      (node (ref "U2") (pin "24") (pinfunction "PC4_24") (pintype "bidirectional"))
    )
    (net (code "66") (name "/TCK-SWCLK") (class "Default")
      (node (ref "J8") (pin "5") (pinfunction "5_5") (pintype "passive"))
      (node (ref "U2") (pin "49") (pinfunction "PA14(JTCK-SWCLK)_49") (pintype "bidirectional"))
    )
    (net (code "67") (name "/TEMP") (class "Default")
      (node (ref "J9") (pin "6") (pinfunction "6_6") (pintype "passive"))
      (node (ref "R29") (pin "1") (pinfunction "1_1") (pintype "passive"))
    )
    (net (code "68") (name "/TMS-SWDIO") (class "Default")
      (node (ref "J8") (pin "4") (pinfunction "4_4") (pintype "passive"))
      (node (ref "U2") (pin "46") (pinfunction "PA13(JTMS-SWDIO)_46") (pintype "bidirectional"))
    )
    (net (code "69") (name "/TRST") (class "Default")
      (node (ref "C13") (pin "1") (pinfunction "1_1") (pintype "passive"))
      (node (ref "J8") (pin "3") (pinfunction "3_3") (pintype "passive"))
      (node (ref "SW1") (pin "2") (pinfunction "2_2") (pintype "passive"))
      (node (ref "U2") (pin "56") (pinfunction "PB4_56") (pintype "bidirectional"))
      (node (ref "U2") (pin "7") (pinfunction "NRST_7") (pintype "bidirectional"))
    )
    (net (code "70") (name "/Temp_in") (class "Default")
      (node (ref "C30") (pin "1") (pinfunction "1_1") (pintype "passive"))
      (node (ref "R29") (pin "2") (pinfunction "2_2") (pintype "passive"))
      (node (ref "R30") (pin "1") (pinfunction "1_1") (pintype "passive"))
      (node (ref "U2") (pin "26") (pinfunction "PB0_26") (pintype "bidirectional"))
    )
    (net (code "71") (name "/USART1_RX") (class "Default")
      (node (ref "U11") (pin "14") (pinfunction "TXD_14") (pintype "passive"))
      (node (ref "U2") (pin "43") (pinfunction "PA10_43") (pintype "bidirectional"))
    )
    (net (code "72") (name "/USART1_TX") (class "Default")
      (node (ref "U11") (pin "13") (pinfunction "RXD_13") (pintype "passive"))
      (node (ref "U2") (pin "42") (pinfunction "PA9_42") (pintype "bidirectional"))
    )
    (net (code "73") (name "/V_reg") (class "Default")
      (node (ref "R22") (pin "1") (pinfunction "1_1") (pintype "passive"))
      (node (ref "U2") (pin "27") (pinfunction "PB1_27") (pintype "bidirectional"))
    )
    (net (code "74") (name "3V3") (class "Default")
      (node (ref "C14") (pin "1") (pinfunction "1_1") (pintype "passive"))
      (node (ref "C16") (pin "1") (pinfunction "1_1") (pintype "passive"))
      (node (ref "C17") (pin "1") (pinfunction "1_1") (pintype "passive"))
      (node (ref "C18") (pin "1") (pinfunction "1_1") (pintype "passive"))
      (node (ref "C19") (pin "1") (pinfunction "1_1") (pintype "passive"))
      (node (ref "C2") (pin "1") (pinfunction "1_1") (pintype "passive"))
      (node (ref "C20") (pin "1") (pinfunction "1_1") (pintype "passive"))
      (node (ref "C25") (pin "1") (pinfunction "1_1") (pintype "passive"))
      (node (ref "C27") (pin "1") (pinfunction "1_1") (pintype "passive"))
      (node (ref "C29") (pin "1") (pinfunction "1_1") (pintype "passive"))
      (node (ref "C31") (pin "2") (pinfunction "2_2") (pintype "passive"))
      (node (ref "D1") (pin "1") (pinfunction "1_1") (pintype "passive"))
      (node (ref "D2") (pin "1") (pinfunction "1_1") (pintype "passive"))
      (node (ref "D3") (pin "1") (pinfunction "1_1") (pintype "passive"))
      (node (ref "D4") (pin "1") (pinfunction "1_1") (pintype "passive"))
      (node (ref "D5") (pin "1") (pinfunction "1_1") (pintype "passive"))
      (node (ref "D6") (pin "1") (pinfunction "1_1") (pintype "passive"))
      (node (ref "D7") (pin "1") (pinfunction "1_1") (pintype "passive"))
      (node (ref "D8") (pin "1") (pinfunction "1_1") (pintype "passive"))
      (node (ref "FB1") (pin "1") (pinfunction "1_1") (pintype "passive"))
      (node (ref "J3") (pin "4") (pintype "passive"))
      (node (ref "L2") (pin "2") (pinfunction "2_2") (pintype "passive"))
      (node (ref "R1") (pin "2") (pinfunction "2_2") (pintype "passive"))
      (node (ref "R14") (pin "1") (pinfunction "1_1") (pintype "passive"))
      (node (ref "R15") (pin "1") (pinfunction "1_1") (pintype "passive"))
      (node (ref "R16") (pin "1") (pinfunction "1_1") (pintype "passive"))
      (node (ref "R17") (pin "1") (pinfunction "1_1") (pintype "passive"))
      (node (ref "R18") (pin "1") (pinfunction "1_1") (pintype "passive"))
      (node (ref "R2") (pin "2") (pinfunction "2_2") (pintype "passive"))
      (node (ref "R3") (pin "2") (pinfunction "2_2") (pintype "passive"))
      (node (ref "R6") (pin "1") (pinfunction "1_1") (pintype "passive"))
      (node (ref "R7") (pin "2") (pinfunction "2_2") (pintype "passive"))
      (node (ref "R9") (pin "2") (pinfunction "2_2") (pintype "passive"))
      (node (ref "U1") (pin "3") (pinfunction "3_3") (pintype "passive"))
      (node (ref "U1") (pin "8") (pinfunction "8_8") (pintype "passive"))
      (node (ref "U10") (pin "1") (pinfunction "VCC_1") (pintype "passive"))
      (node (ref "U11") (pin "8") (pinfunction "VIN_8") (pintype "passive"))
      (node (ref "U2") (pin "19") (pinfunction "VDD_4_19") (pintype "power_in"))
      (node (ref "U2") (pin "32") (pinfunction "VDD_1_32") (pintype "power_in"))
      (node (ref "U2") (pin "48") (pinfunction "VDD_2_48") (pintype "power_in"))
      (node (ref "U2") (pin "64") (pinfunction "VDD_3_64") (pintype "power_in"))
      (node (ref "U3") (pin "25") (pinfunction "~{RST}_25") (pintype "passive"))
      (node (ref "U3") (pin "28") (pinfunction "Vdd_28") (pintype "passive"))
      (node (ref "U3") (pin "3") (pinfunction "A1_3") (pintype "passive"))
      (node (ref "U5") (pin "8") (pinfunction "VCC_8") (pintype "passive"))
      (node (ref "U8") (pin "16") (pinfunction "VDD_16") (pintype "passive"))
      (node (ref "U9") (pin "16") (pinfunction "VDD_16") (pintype "passive"))
    )
    (net (code "75") (name "3V3A") (class "Default")
      (node (ref "C21") (pin "1") (pinfunction "1_1") (pintype "passive"))
      (node (ref "FB1") (pin "2") (pinfunction "2_2") (pintype "passive"))
      (node (ref "U2") (pin "13") (pinfunction "VDDA_13") (pintype "power_in"))
    )
    (net (code "76") (name "GND") (class "Default")
      (node (ref "C1") (pin "2") (pinfunction "2_2") (pintype "passive"))
      (node (ref "C10") (pin "1") (pinfunction "1_1") (pintype "passive"))
      (node (ref "C11") (pin "1") (pinfunction "1_1") (pintype "passive"))
      (node (ref "C12") (pin "1") (pinfunction "1_1") (pintype "passive"))
      (node (ref "C13") (pin "2") (pinfunction "2_2") (pintype "passive"))
      (node (ref "C14") (pin "2") (pinfunction "2_2") (pintype "passive"))
      (node (ref "C15") (pin "2") (pinfunction "2_2") (pintype "passive"))
      (node (ref "C16") (pin "2") (pinfunction "2_2") (pintype "passive"))
      (node (ref "C17") (pin "2") (pinfunction "2_2") (pintype "passive"))
      (node (ref "C18") (pin "2") (pinfunction "2_2") (pintype "passive"))
      (node (ref "C19") (pin "2") (pinfunction "2_2") (pintype "passive"))
      (node (ref "C2") (pin "2") (pinfunction "2_2") (pintype "passive"))
      (node (ref "C20") (pin "2") (pinfunction "2_2") (pintype "passive"))
      (node (ref "C21") (pin "2") (pinfunction "2_2") (pintype "passive"))
      (node (ref "C22") (pin "2") (pinfunction "2_2") (pintype "passive"))
      (node (ref "C25") (pin "2") (pinfunction "2_2") (pintype "passive"))
      (node (ref "C26") (pin "1") (pinfunction "1_1") (pintype "passive"))
      (node (ref "C27") (pin "2") (pinfunction "2_2") (pintype "passive"))
      (node (ref "C28") (pin "1") (pinfunction "1_1") (pintype "passive"))
      (node (ref "C29") (pin "2") (pinfunction "2_2") (pintype "passive"))
      (node (ref "C30") (pin "2") (pinfunction "2_2") (pintype "passive"))
      (node (ref "C31") (pin "1") (pinfunction "1_1") (pintype "passive"))
      (node (ref "C32") (pin "2") (pinfunction "2_2") (pintype "passive"))
      (node (ref "C4") (pin "2") (pinfunction "2_2") (pintype "passive"))
      (node (ref "C6") (pin "2") (pinfunction "2_2") (pintype "passive"))
      (node (ref "C7") (pin "1") (pinfunction "1_1") (pintype "passive"))
      (node (ref "C8") (pin "2") (pinfunction "2_2") (pintype "passive"))
      (node (ref "C9") (pin "1") (pinfunction "1_1") (pintype "passive"))
      (node (ref "D10") (pin "1") (pinfunction "1_1") (pintype "passive"))
      (node (ref "D34") (pin "1") (pinfunction "1_1") (pintype "passive"))
      (node (ref "D9") (pin "1") (pinfunction "A_1") (pintype "passive"))
      (node (ref "J1") (pin "1") (pintype "passive"))
      (node (ref "J1") (pin "4") (pintype "passive"))
      (node (ref "J2") (pin "1") (pintype "passive"))
      (node (ref "J2") (pin "4") (pintype "passive"))
      (node (ref "J3") (pin "1") (pintype "passive"))
      (node (ref "J5") (pin "1") (pintype "passive"))
      (node (ref "J5") (pin "4") (pintype "passive"))
      (node (ref "J6") (pin "1") (pintype "passive"))
      (node (ref "J6") (pin "4") (pintype "passive"))
      (node (ref "J7") (pin "1") (pintype "passive"))
      (node (ref "J7") (pin "4") (pintype "passive"))
      (node (ref "J8") (pin "1") (pinfunction "1_1") (pintype "passive"))
      (node (ref "J9") (pin "2") (pinfunction "2_2") (pintype "passive"))
      (node (ref "R10") (pin "2") (pinfunction "2_2") (pintype "passive"))
      (node (ref "R11") (pin "2") (pinfunction "2_2") (pintype "passive"))
      (node (ref "R13") (pin "1") (pinfunction "1_1") (pintype "passive"))
      (node (ref "R30") (pin "2") (pinfunction "2_2") (pintype "passive"))
      (node (ref "R31") (pin "1") (pinfunction "1_1") (pintype "passive"))
      (node (ref "R32") (pin "1") (pinfunction "1_1") (pintype "passive"))
      (node (ref "R33") (pin "1") (pinfunction "1_1") (pintype "passive"))
      (node (ref "R34") (pin "1") (pinfunction "1_1") (pintype "passive"))
      (node (ref "R35") (pin "1") (pinfunction "1_1") (pintype "passive"))
      (node (ref "R36") (pin "1") (pinfunction "1_1") (pintype "passive"))
      (node (ref "R37") (pin "1") (pinfunction "1_1") (pintype "passive"))
      (node (ref "R38") (pin "1") (pinfunction "1_1") (pintype "passive"))
      (node (ref "R39") (pin "1") (pinfunction "1_1") (pintype "passive"))
      (node (ref "R4") (pin "1") (pinfunction "1_1") (pintype "passive"))
      (node (ref "R40") (pin "1") (pinfunction "1_1") (pintype "passive"))
      (node (ref "R41") (pin "1") (pinfunction "1_1") (pintype "passive"))
      (node (ref "R42") (pin "1") (pinfunction "1_1") (pintype "passive"))
      (node (ref "R43") (pin "1") (pinfunction "1_1") (pintype "passive"))
      (node (ref "R44") (pin "1") (pinfunction "1_1") (pintype "passive"))
      (node (ref "R45") (pin "1") (pinfunction "1_1") (pintype "passive"))
      (node (ref "R5") (pin "2") (pinfunction "2_2") (pintype "passive"))
      (node (ref "R8") (pin "1") (pinfunction "1_1") (pintype "passive"))
      (node (ref "SW1") (pin "4") (pinfunction "4_4") (pintype "passive"))
      (node (ref "U10") (pin "11") (pinfunction "EI_11") (pintype "passive"))
      (node (ref "U10") (pin "13") (pinfunction "MODE_13") (pintype "passive"))
      (node (ref "U10") (pin "14") (pinfunction "FI_14") (pintype "passive"))
      (node (ref "U10") (pin "8") (pinfunction "VSS_8") (pintype "passive"))
      (node (ref "U10") (pin "9") (pinfunction "DI_9") (pintype "passive"))
      (node (ref "U11") (pin "7") (pinfunction "GND_7") (pintype "passive"))
      (node (ref "U2") (pin "12") (pinfunction "VSSA_12") (pintype "power_in"))
      (node (ref "U2") (pin "18") (pinfunction "VSS_4_18") (pintype "power_in"))
      (node (ref "U2") (pin "63") (pinfunction "VSS_3_63") (pintype "power_in"))
      (node (ref "U3") (pin "10") (pinfunction "Vss_10") (pintype "passive"))
      (node (ref "U3") (pin "19") (pinfunction "Vss_19") (pintype "passive"))
      (node (ref "U3") (pin "2") (pinfunction "A0_2") (pintype "passive"))
      (node (ref "U3") (pin "24") (pinfunction "Vss_24") (pintype "passive"))
      (node (ref "U3") (pin "4") (pinfunction "A2_4") (pintype "passive"))
      (node (ref "U3") (pin "5") (pinfunction "~{OE}_5") (pintype "passive"))
      (node (ref "U4") (pin "7") (pinfunction "GND_7") (pintype "passive"))
      (node (ref "U5") (pin "4") (pinfunction "GND_4") (pintype "passive"))
      (node (ref "U5") (pin "9") (pinfunction "PAD_9") (pintype "passive"))
      (node (ref "U8") (pin "13") (pinfunction "MODE_13") (pintype "passive"))
      (node (ref "U8") (pin "8") (pinfunction "VSS_8") (pintype "passive"))
      (node (ref "U9") (pin "13") (pinfunction "MODE_13") (pintype "passive"))
      (node (ref "U9") (pin "8") (pinfunction "VSS_8") (pintype "passive"))
      (node (ref "X1") (pin "2") (pinfunction "2_2") (pintype "passive"))
      (node (ref "X1") (pin "4") (pinfunction "4_4") (pintype "passive"))
    )
    (net (code "77") (name "Net-(C1-Pad1)") (class "Default")
      (node (ref "C1") (pin "1") (pinfunction "1_1") (pintype "passive"))
      (node (ref "J3") (pin "2") (pintype "passive"))
      (node (ref "J3") (pin "3") (pintype "passive"))
      (node (ref "R22") (pin "2") (pinfunction "2_2") (pintype "passive"))
    )
    (net (code "78") (name "Net-(C4-Pad1)") (class "Default")
      (node (ref "C4") (pin "1") (pinfunction "1_1") (pintype "passive"))
      (node (ref "L1") (pin "2") (pinfunction "2_2") (pintype "passive"))
      (node (ref "L2") (pin "1") (pinfunction "1_1") (pintype "passive"))
      (node (ref "R12") (pin "2") (pinfunction "2_2") (pintype "passive"))
    )
    (net (code "79") (name "Net-(C5-Pad2)") (class "Default")
      (node (ref "C5") (pin "2") (pinfunction "2_2") (pintype "passive"))
      (node (ref "R11") (pin "1") (pinfunction "1_1") (pintype "passive"))
    )
    (net (code "80") (name "Net-(D9-K)") (class "Default")
      (node (ref "C3") (pin "1") (pinfunction "1_1") (pintype "passive"))
      (node (ref "D9") (pin "2") (pinfunction "K_2") (pintype "passive"))
      (node (ref "L1") (pin "1") (pinfunction "1_1") (pintype "passive"))
      (node (ref "U4") (pin "8") (pinfunction "PH_8") (pintype "passive"))
    )
    (net (code "81") (name "Net-(D32-A)") (class "Default")
      (node (ref "D32") (pin "1") (pinfunction "A_1") (pintype "passive"))
      (node (ref "J9") (pin "1") (pinfunction "1_1") (pintype "passive"))
    )
    (net (code "82") (name "Net-(J1-Pad2)") (class "Default")
      (node (ref "J1") (pin "2") (pintype "passive"))
      (node (ref "J1") (pin "3") (pintype "passive"))
      (node (ref "R1") (pin "1") (pinfunction "1_1") (pintype "passive"))
      (node (ref "R25") (pin "1") (pinfunction "1_1") (pintype "passive"))
    )
    (net (code "83") (name "Net-(J2-Pad2)") (class "Default")
      (node (ref "J2") (pin "2") (pintype "passive"))
      (node (ref "R2") (pin "1") (pinfunction "1_1") (pintype "passive"))
      (node (ref "R23") (pin "1") (pinfunction "1_1") (pintype "passive"))
    )
    (net (code "84") (name "Net-(J2-Pad3)") (class "Default")
      (node (ref "J2") (pin "3") (pintype "passive"))
      (node (ref "R24") (pin "1") (pinfunction "1_1") (pintype "passive"))
      (node (ref "R3") (pin "1") (pinfunction "1_1") (pintype "passive"))
    )
    (net (code "85") (name "Net-(J5-Pad2)") (class "Default")
      (node (ref "J5") (pin "2") (pintype "passive"))
      (node (ref "J5") (pin "3") (pintype "passive"))
      (node (ref "R21") (pin "1") (pinfunction "1_1") (pintype "passive"))
      (node (ref "R6") (pin "2") (pinfunction "2_2") (pintype "passive"))
    )
    (net (code "86") (name "Net-(J6-Pad2)") (class "Default")
      (node (ref "J6") (pin "2") (pintype "passive"))
      (node (ref "J6") (pin "3") (pintype "passive"))
      (node (ref "R27") (pin "1") (pinfunction "1_1") (pintype "passive"))
      (node (ref "R7") (pin "1") (pinfunction "1_1") (pintype "passive"))
    )
    (net (code "87") (name "Net-(J7-Pad2)") (class "Default")
      (node (ref "J7") (pin "2") (pintype "passive"))
      (node (ref "J7") (pin "3") (pintype "passive"))
      (node (ref "R28") (pin "1") (pinfunction "1_1") (pintype "passive"))
      (node (ref "R9") (pin "1") (pinfunction "1_1") (pintype "passive"))
    )
    (net (code "88") (name "Net-(U2A-PB5)") (class "Default")
      (node (ref "TP1") (pin "1") (pinfunction "1_1") (pintype "passive"))
      (node (ref "U2") (pin "57") (pinfunction "PB5_57") (pintype "bidirectional"))
    )
    (net (code "89") (name "Net-(U2A-PB6)") (class "Default")
      (node (ref "TP2") (pin "1") (pinfunction "1_1") (pintype "passive"))
      (node (ref "U2") (pin "58") (pinfunction "PB6_58") (pintype "bidirectional"))
    )
    (net (code "90") (name "Net-(U2A-PB7)") (class "Default")
      (node (ref "TP3") (pin "1") (pinfunction "1_1") (pintype "passive"))
      (node (ref "U2") (pin "59") (pinfunction "PB7_59") (pintype "bidirectional"))
    )
    (net (code "91") (name "Net-(U2B-VCAP_1)") (class "Default")
      (node (ref "C10") (pin "2") (pinfunction "2_2") (pintype "passive"))
      (node (ref "U2") (pin "31") (pinfunction "VCAP_1_31") (pintype "power_in"))
    )
    (net (code "92") (name "Net-(U2B-VCAP_2)") (class "Default")
      (node (ref "C9") (pin "2") (pinfunction "2_2") (pintype "passive"))
      (node (ref "U2") (pin "47") (pinfunction "VCAP_2_47") (pintype "power_in"))
    )
    (net (code "93") (name "Net-(U3-LED0)") (class "Default")
      (node (ref "TP4") (pin "1") (pinfunction "1_1") (pintype "passive"))
      (node (ref "U3") (pin "6") (pinfunction "LED0_6") (pintype "passive"))
    )
    (net (code "94") (name "Net-(U3-LED1)") (class "Default")
      (node (ref "TP5") (pin "1") (pinfunction "1_1") (pintype "passive"))
      (node (ref "U3") (pin "7") (pinfunction "LED1_7") (pintype "passive"))
    )
    (net (code "95") (name "Net-(U3-Rext)") (class "Default")
      (node (ref "R8") (pin "2") (pinfunction "2_2") (pintype "passive"))
      (node (ref "U3") (pin "1") (pinfunction "Rext_1") (pintype "passive"))
    )
    (net (code "96") (name "Net-(U4-Boot)") (class "Default")
      (node (ref "C3") (pin "2") (pinfunction "2_2") (pintype "passive"))
      (node (ref "U4") (pin "1") (pinfunction "Boot_1") (pintype "passive"))
    )
    (net (code "97") (name "Net-(U4-COMP)") (class "Default")
      (node (ref "C5") (pin "1") (pinfunction "1_1") (pintype "passive"))
      (node (ref "C6") (pin "1") (pinfunction "1_1") (pintype "passive"))
      (node (ref "U4") (pin "6") (pinfunction "COMP_6") (pintype "passive"))
    )
    (net (code "98") (name "Net-(U4-SS)") (class "Default")
      (node (ref "C8") (pin "1") (pinfunction "1_1") (pintype "passive"))
      (node (ref "U4") (pin "4") (pinfunction "SS_4") (pintype "passive"))
    )
    (net (code "99") (name "Net-(U4-VSENSE)") (class "Default")
      (node (ref "R12") (pin "1") (pinfunction "1_1") (pintype "passive"))
      (node (ref "R13") (pin "2") (pinfunction "2_2") (pintype "passive"))
      (node (ref "U4") (pin "5") (pinfunction "VSENSE_5") (pintype "passive"))
    )
    (net (code "100") (name "Net-(U5-~{HOLD})") (class "Default")
      (node (ref "R17") (pin "2") (pinfunction "2_2") (pintype "passive"))
      (node (ref "U5") (pin "7") (pinfunction "~{HOLD}_7") (pintype "passive"))
    )
    (net (code "101") (name "Net-(U5-~{WP})") (class "Default")
      (node (ref "R18") (pin "2") (pinfunction "2_2") (pintype "passive"))
      (node (ref "U5") (pin "3") (pinfunction "~{WP}_3") (pintype "passive"))
    )
    (net (code "102") (name "VBAT") (class "Default")
      (node (ref "C22") (pin "1") (pinfunction "1_1") (pintype "passive"))
      (node (ref "U2") (pin "1") (pinfunction "VBAT_1") (pintype "power_in"))
    )
    (net (code "103") (name "VIN") (class "Default")
      (node (ref "C15") (pin "1") (pinfunction "1_1") (pintype "passive"))
      (node (ref "C26") (pin "2") (pinfunction "2_2") (pintype "passive"))
      (node (ref "C28") (pin "2") (pinfunction "2_2") (pintype "passive"))
      (node (ref "C32") (pin "1") (pinfunction "1_1") (pintype "passive"))
      (node (ref "C7") (pin "2") (pinfunction "2_2") (pintype "passive"))
      (node (ref "D10") (pin "2") (pinfunction "2_2") (pintype "passive"))
      (node (ref "D32") (pin "2") (pinfunction "K_2") (pintype "passive"))
      (node (ref "D33") (pin "2") (pinfunction "K_2") (pintype "passive"))
      (node (ref "J4") (pin "1") (pintype "passive"))
      (node (ref "J4") (pin "4") (pintype "passive"))
      (node (ref "U10") (pin "16") (pinfunction "VDD_16") (pintype "passive"))
      (node (ref "U4") (pin "2") (pinfunction "Vin_2") (pintype "passive"))
      (node (ref "U8") (pin "1") (pinfunction "VCC_1") (pintype "passive"))
      (node (ref "U9") (pin "1") (pinfunction "VCC_1") (pintype "passive"))
    )
    (net (code "104") (name "unconnected-(J9-Pad8)") (class "Default")
      (node (ref "J9") (pin "8") (pinfunction "8_8") (pintype "passive+no_connect"))
    )
    (net (code "105") (name "unconnected-(SW1-Pad1)") (class "Default")
      (node (ref "SW1") (pin "1") (pinfunction "1_1") (pintype "passive+no_connect"))
    )
    (net (code "106") (name "unconnected-(SW1-Pad3)") (class "Default")
      (node (ref "SW1") (pin "3") (pinfunction "3_3") (pintype "passive+no_connect"))
    )
    (net (code "107") (name "unconnected-(U2A-PA0-WKUP(PA0)-Pad14)") (class "Default")
      (node (ref "U2") (pin "14") (pinfunction "PA0-WKUP(PA0)_14") (pintype "bidirectional+no_connect"))
    )
    (net (code "108") (name "unconnected-(U2A-PA11-Pad44)") (class "Default")
      (node (ref "U2") (pin "44") (pinfunction "PA11_44") (pintype "bidirectional+no_connect"))
    )
    (net (code "109") (name "unconnected-(U2A-PA12-Pad45)") (class "Default")
      (node (ref "U2") (pin "45") (pinfunction "PA12_45") (pintype "bidirectional+no_connect"))
    )
    (net (code "110") (name "unconnected-(U2A-PB3(JTDO{slash}TRACESWO)-Pad55)") (class "Default")
      (node (ref "U2") (pin "55") (pinfunction "PB3(JTDO/TRACESWO)_55") (pintype "bidirectional+no_connect"))
    )
    (net (code "111") (name "unconnected-(U2A-PB10-Pad29)") (class "Default")
      (node (ref "U2") (pin "29") (pinfunction "PB10_29") (pintype "bidirectional+no_connect"))
    )
    (net (code "112") (name "unconnected-(U2A-PB11-Pad30)") (class "Default")
      (node (ref "U2") (pin "30") (pinfunction "PB11_30") (pintype "bidirectional+no_connect"))
    )
    (net (code "113") (name "unconnected-(U2A-PC13-Pad2)") (class "Default")
      (node (ref "U2") (pin "2") (pinfunction "PC13_2") (pintype "bidirectional+no_connect"))
    )
    (net (code "114") (name "unconnected-(U2A-PC14-OSC32_IN(PC14)-Pad3)") (class "Default")
      (node (ref "U2") (pin "3") (pinfunction "PC14-OSC32_IN(PC14)_3") (pintype "bidirectional+no_connect"))
    )
    (net (code "115") (name "unconnected-(U2A-PC15-OSC32_OUT(PC15)-Pad4)") (class "Default")
      (node (ref "U2") (pin "4") (pinfunction "PC15-OSC32_OUT(PC15)_4") (pintype "bidirectional+no_connect"))
    )
    (net (code "116") (name "unconnected-(U2A-PD2-Pad54)") (class "Default")
      (node (ref "U2") (pin "54") (pinfunction "PD2_54") (pintype "bidirectional+no_connect"))
    )
    (net (code "117") (name "unconnected-(U3-LED2-Pad8)") (class "Default")
      (node (ref "U3") (pin "8") (pinfunction "LED2_8") (pintype "passive+no_connect"))
    )
    (net (code "118") (name "unconnected-(U4-EN-Pad3)") (class "Default")
      (node (ref "U4") (pin "3") (pinfunction "EN_3") (pintype "passive+no_connect"))
    )
    (net (code "119") (name "unconnected-(U10-DO-Pad10)") (class "Default")
      (node (ref "U10") (pin "10") (pinfunction "DO_10") (pintype "passive+no_connect"))
    )
    (net (code "120") (name "unconnected-(U10-EO-Pad12)") (class "Default")
      (node (ref "U10") (pin "12") (pinfunction "EO_12") (pintype "passive+no_connect"))
    )
    (net (code "121") (name "unconnected-(U10-FO-Pad15)") (class "Default")
      (node (ref "U10") (pin "15") (pinfunction "FO_15") (pintype "passive+no_connect"))
    )
    (net (code "122") (name "unconnected-(U11-BOOT-Pad9)") (class "Default")
      (node (ref "U11") (pin "9") (pinfunction "BOOT_9") (pintype "passive+no_connect"))
    )
    (net (code "123") (name "unconnected-(U11-CTS-Pad11)") (class "Default")
      (node (ref "U11") (pin "11") (pinfunction "CTS_11") (pintype "passive+no_connect"))
    )
    (net (code "124") (name "unconnected-(U11-GPIO1-Pad1)") (class "Default")
      (node (ref "U11") (pin "1") (pinfunction "GPIO1_1") (pintype "passive+no_connect"))
    )
    (net (code "125") (name "unconnected-(U11-GPIO2-Pad2)") (class "Default")
      (node (ref "U11") (pin "2") (pinfunction "GPIO2_2") (pintype "passive+no_connect"))
    )
    (net (code "126") (name "unconnected-(U11-GPIO3-Pad3)") (class "Default")
      (node (ref "U11") (pin "3") (pinfunction "GPIO3_3") (pintype "passive+no_connect"))
    )
    (net (code "127") (name "unconnected-(U11-GPIO4-Pad4)") (class "Default")
      (node (ref "U11") (pin "4") (pinfunction "GPIO4_4") (pintype "passive+no_connect"))
    )
    (net (code "128") (name "unconnected-(U11-GPIO5-Pad5)") (class "Default")
      (node (ref "U11") (pin "5") (pinfunction "GPIO5_5") (pintype "passive+no_connect"))
    )
    (net (code "129") (name "unconnected-(U11-GPIO6-Pad6)") (class "Default")
      (node (ref "U11") (pin "6") (pinfunction "GPIO6_6") (pintype "passive+no_connect"))
    )
    (net (code "130") (name "unconnected-(U11-GPIO7-Pad16)") (class "Default")
      (node (ref "U11") (pin "16") (pinfunction "GPIO7_16") (pintype "passive+no_connect"))
    )
    (net (code "131") (name "unconnected-(U11-LPO-Pad15)") (class "Default")
      (node (ref "U11") (pin "15") (pinfunction "LPO_15") (pintype "passive+no_connect"))
    )
    (net (code "132") (name "unconnected-(U11-RST-Pad10)") (class "Default")
      (node (ref "U11") (pin "10") (pinfunction "RST_10") (pintype "passive+no_connect"))
    )
    (net (code "133") (name "unconnected-(U11-RTS-Pad12)") (class "Default")
      (node (ref "U11") (pin "12") (pinfunction "RTS_12") (pintype "passive+no_connect"))
    )
  )
)
